# modem.net
KiCad netlist of a schematic drawn in Altium Designer
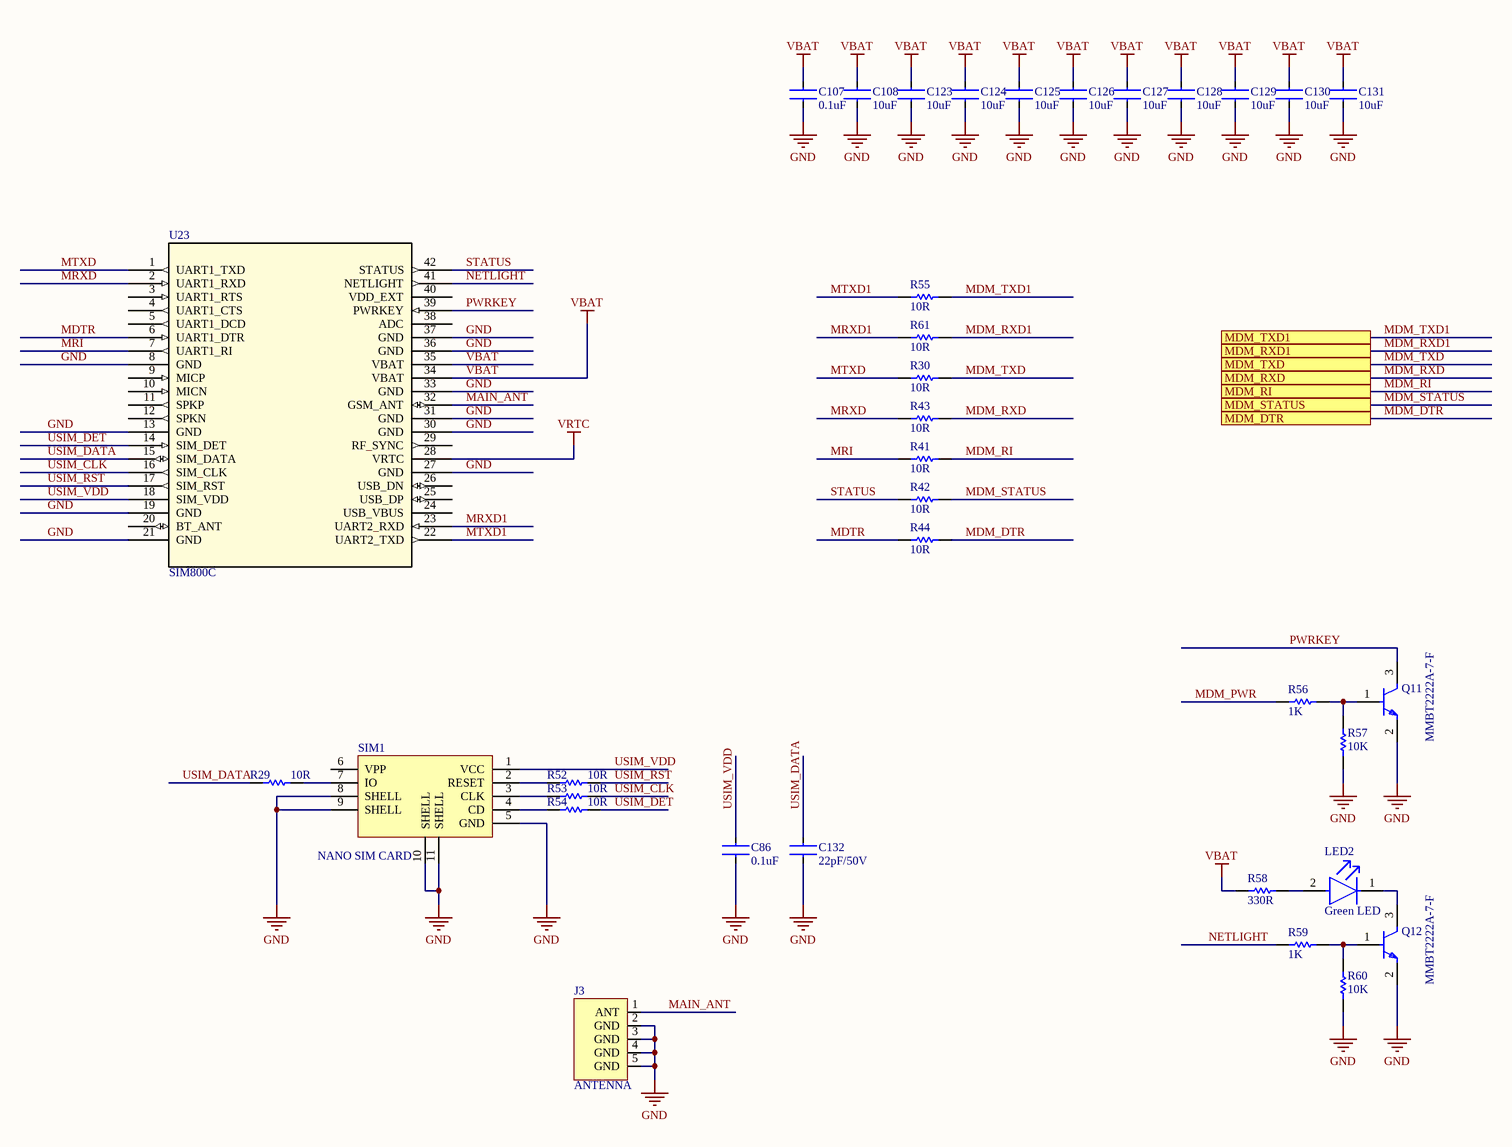
[diagram p0: modem.SchDoc]

(export (version "E")
  (design (tool "Eeschema 10.0.6"))
  (components
    (comp (ref "C86")
      (value "0.1uF")
      (footprint "C0402")
      (description "Ceramic capacitor SMD-1206 100nF /50V X7R# K +-10%, Samsung, RoHS")
      (fields
        (field (name "MANUFACTURER") "Samsung")
        (field (name "MANUFACTURER PART NUMBER") "CL31B104KBCNNNC")
      )
      (libsource (lib "afra") (part "CL31B104KBCNNNC"))
    )
    (comp (ref "C107")
      (value "0.1uF")
      (footprint "C0402")
      (description "Ceramic capacitor SMD-1206 100nF /50V X7R# K +-10%, Samsung, RoHS")
      (fields
        (field (name "MANUFACTURER") "Samsung")
        (field (name "MANUFACTURER PART NUMBER") "CL31B104KBCNNNC")
      )
      (libsource (lib "afra") (part "CL31B104KBCNNNC"))
    )
    (comp (ref "C108")
      (value "10uF")
      (footprint "C0402")
      (description "Cap Ceramic 10uF 16V X7R 10% Pad SMD 1206 125°C T/R")
      (fields
        (field (name "MANUFACTURER") "Samsung")
        (field (name "MANUFACTURER PART NUMBER") "CL31B106KOHNNNE")
      )
      (libsource (lib "afra") (part "CL31B106KOHNNNE"))
    )
    (comp (ref "C123")
      (value "10uF")
      (footprint "C0402")
      (description "Cap Ceramic 10uF 16V X7R 10% Pad SMD 1206 125°C T/R")
      (fields
        (field (name "MANUFACTURER") "Samsung")
        (field (name "MANUFACTURER PART NUMBER") "CL31B106KOHNNNE")
      )
      (libsource (lib "afra") (part "CL31B106KOHNNNE"))
    )
    (comp (ref "C124")
      (value "10uF")
      (footprint "C0402")
      (description "Cap Ceramic 10uF 16V X7R 10% Pad SMD 1206 125°C T/R")
      (fields
        (field (name "MANUFACTURER") "Samsung")
        (field (name "MANUFACTURER PART NUMBER") "CL31B106KOHNNNE")
      )
      (libsource (lib "afra") (part "CL31B106KOHNNNE"))
    )
    (comp (ref "C125")
      (value "10uF")
      (footprint "C0402")
      (description "Cap Ceramic 10uF 16V X7R 10% Pad SMD 1206 125°C T/R")
      (fields
        (field (name "MANUFACTURER") "Samsung")
        (field (name "MANUFACTURER PART NUMBER") "CL31B106KOHNNNE")
      )
      (libsource (lib "afra") (part "CL31B106KOHNNNE"))
    )
    (comp (ref "C126")
      (value "10uF")
      (footprint "C0402")
      (description "Cap Ceramic 10uF 16V X7R 10% Pad SMD 1206 125°C T/R")
      (fields
        (field (name "MANUFACTURER") "Samsung")
        (field (name "MANUFACTURER PART NUMBER") "CL31B106KOHNNNE")
      )
      (libsource (lib "afra") (part "CL31B106KOHNNNE"))
    )
    (comp (ref "C127")
      (value "10uF")
      (footprint "C0402")
      (description "Cap Ceramic 10uF 16V X7R 10% Pad SMD 1206 125°C T/R")
      (fields
        (field (name "MANUFACTURER") "Samsung")
        (field (name "MANUFACTURER PART NUMBER") "CL31B106KOHNNNE")
      )
      (libsource (lib "afra") (part "CL31B106KOHNNNE"))
    )
    (comp (ref "C128")
      (value "10uF")
      (footprint "C0402")
      (description "Cap Ceramic 10uF 16V X7R 10% Pad SMD 1206 125°C T/R")
      (fields
        (field (name "MANUFACTURER") "Samsung")
        (field (name "MANUFACTURER PART NUMBER") "CL31B106KOHNNNE")
      )
      (libsource (lib "afra") (part "CL31B106KOHNNNE"))
    )
    (comp (ref "C129")
      (value "10uF")
      (footprint "C0402")
      (description "Cap Ceramic 10uF 16V X7R 10% Pad SMD 1206 125°C T/R")
      (fields
        (field (name "MANUFACTURER") "Samsung")
        (field (name "MANUFACTURER PART NUMBER") "CL31B106KOHNNNE")
      )
      (libsource (lib "afra") (part "CL31B106KOHNNNE"))
    )
    (comp (ref "C130")
      (value "10uF")
      (footprint "C0402")
      (description "Cap Ceramic 10uF 16V X7R 10% Pad SMD 1206 125°C T/R")
      (fields
        (field (name "MANUFACTURER") "Samsung")
        (field (name "MANUFACTURER PART NUMBER") "CL31B106KOHNNNE")
      )
      (libsource (lib "afra") (part "CL31B106KOHNNNE"))
    )
    (comp (ref "C131")
      (value "10uF")
      (footprint "C0402")
      (description "Cap Ceramic 10uF 16V X7R 10% Pad SMD 1206 125°C T/R")
      (fields
        (field (name "MANUFACTURER") "Samsung")
        (field (name "MANUFACTURER PART NUMBER") "CL31B106KOHNNNE")
      )
      (libsource (lib "afra") (part "CL31B106KOHNNNE"))
    )
    (comp (ref "C132")
      (value "22pF/50V")
      (footprint "C0402")
      (description "Cap Ceramic 22pF 50V C0G 5% SMD 1206 125°C Paper T/R")
      (fields
        (field (name "MANUFACTURER") "Samsung")
        (field (name "MANUFACTURER PART NUMBER") "CL31C220JBCNNNC")
      )
      (libsource (lib "afra") (part "CL31C220JBCNNNC"))
    )
    (comp (ref "J3") (value "ANTENNA") (footprint "Antenna") (libsource (lib "afra") (part "antenna")))
    (comp (ref "LED2")
      (value "Green LED")
      (footprint "SMD_LED_1206")
      (description "LED GREEN CLEAR 1206 SMD")
      (fields
        (field (name "MANUFACTURER") "Vishay Lite-On")
        (field (name "MANUFACTURER PART NUMBER") "LTST-C150GKT")
      )
      (libsource (lib "afra") (part "LTST-C150GKT"))
    )
    (comp (ref "Q11")
      (value "MMBT2222A-7-F")
      (footprint "SOT-23-3L_AOS")
      (description "NPN Ic=600mA Vceo=40V hfe=100~300 fT=300MHz P=310mW SOT-23")
      (fields (field (name "MANUFACTURER") "Diodes") (field (name "VOLTAGE") "40V"))
      (libsource (lib "afra") (part "MMBT2222A-7-F"))
    )
    (comp (ref "Q12")
      (value "MMBT2222A-7-F")
      (footprint "SOT-23-3L_AOS")
      (description "NPN Ic=600mA Vceo=40V hfe=100~300 fT=300MHz P=310mW SOT-23")
      (fields (field (name "MANUFACTURER") "Diodes") (field (name "VOLTAGE") "40V"))
      (libsource (lib "afra") (part "MMBT2222A-7-F"))
    )
    (comp (ref "R29")
      (value "10R")
      (footprint "R0402")
      (description "Res Thick Film 1206 10 Ohm 1% 0.25W(1/4W) +/-200ppm/ßC Epoxy SMD T/R")
      (fields
        (field (name "MANUFACTURER") "Yageo")
        (field (name "MANUFACTURER PART NUMBER") "RC1206FR-0710RL")
      )
      (libsource (lib "afra") (part "RC1206FR-0710RL"))
    )
    (comp (ref "R30")
      (value "10R")
      (footprint "R0402")
      (description "Res Thick Film 1206 10 Ohm 1% 0.25W(1/4W) +/-200ppm/ßC Epoxy SMD T/R")
      (fields
        (field (name "MANUFACTURER") "Yageo")
        (field (name "MANUFACTURER PART NUMBER") "RC1206FR-0710RL")
      )
      (libsource (lib "afra") (part "RC1206FR-0710RL"))
    )
    (comp (ref "R41")
      (value "10R")
      (footprint "R0402")
      (description "Res Thick Film 1206 10 Ohm 1% 0.25W(1/4W) +/-200ppm/ßC Epoxy SMD T/R")
      (fields
        (field (name "MANUFACTURER") "Yageo")
        (field (name "MANUFACTURER PART NUMBER") "RC1206FR-0710RL")
      )
      (libsource (lib "afra") (part "RC1206FR-0710RL"))
    )
    (comp (ref "R42")
      (value "10R")
      (footprint "R0402")
      (description "Res Thick Film 1206 10 Ohm 1% 0.25W(1/4W) +/-200ppm/ßC Epoxy SMD T/R")
      (fields
        (field (name "MANUFACTURER") "Yageo")
        (field (name "MANUFACTURER PART NUMBER") "RC1206FR-0710RL")
      )
      (libsource (lib "afra") (part "RC1206FR-0710RL"))
    )
    (comp (ref "R43")
      (value "10R")
      (footprint "R0402")
      (description "Res Thick Film 1206 10 Ohm 1% 0.25W(1/4W) +/-200ppm/ßC Epoxy SMD T/R")
      (fields
        (field (name "MANUFACTURER") "Yageo")
        (field (name "MANUFACTURER PART NUMBER") "RC1206FR-0710RL")
      )
      (libsource (lib "afra") (part "RC1206FR-0710RL"))
    )
    (comp (ref "R44")
      (value "10R")
      (footprint "R0402")
      (description "Res Thick Film 1206 10 Ohm 1% 0.25W(1/4W) +/-200ppm/ßC Epoxy SMD T/R")
      (fields
        (field (name "MANUFACTURER") "Yageo")
        (field (name "MANUFACTURER PART NUMBER") "RC1206FR-0710RL")
      )
      (libsource (lib "afra") (part "RC1206FR-0710RL"))
    )
    (comp (ref "R52")
      (value "10R")
      (footprint "R0402")
      (description "Res Thick Film 1206 10 Ohm 1% 0.25W(1/4W) +/-200ppm/ßC Epoxy SMD T/R")
      (fields
        (field (name "MANUFACTURER") "Yageo")
        (field (name "MANUFACTURER PART NUMBER") "RC1206FR-0710RL")
      )
      (libsource (lib "afra") (part "RC1206FR-0710RL"))
    )
    (comp (ref "R53")
      (value "10R")
      (footprint "R0402")
      (description "Res Thick Film 1206 10 Ohm 1% 0.25W(1/4W) +/-200ppm/ßC Epoxy SMD T/R")
      (fields
        (field (name "MANUFACTURER") "Yageo")
        (field (name "MANUFACTURER PART NUMBER") "RC1206FR-0710RL")
      )
      (libsource (lib "afra") (part "RC1206FR-0710RL"))
    )
    (comp (ref "R54")
      (value "10R")
      (footprint "R0402")
      (description "Res Thick Film 1206 10 Ohm 1% 0.25W(1/4W) +/-200ppm/ßC Epoxy SMD T/R")
      (fields
        (field (name "MANUFACTURER") "Yageo")
        (field (name "MANUFACTURER PART NUMBER") "RC1206FR-0710RL")
      )
      (libsource (lib "afra") (part "RC1206FR-0710RL"))
    )
    (comp (ref "R55")
      (value "10R")
      (footprint "R0402")
      (description "Res Thick Film 1206 10 Ohm 1% 0.25W(1/4W) +/-200ppm/ßC Epoxy SMD T/R")
      (fields
        (field (name "MANUFACTURER") "Yageo")
        (field (name "MANUFACTURER PART NUMBER") "RC1206FR-0710RL")
      )
      (libsource (lib "afra") (part "RC1206FR-0710RL"))
    )
    (comp (ref "R56")
      (value "1K")
      (footprint "R0402")
      (description "In a Pack of 5000, 1K 1206 Thick Film SMD Resistor ±1% 0.25W - RC1206FR-071KL")
      (fields
        (field (name "MANUFACTURER") "Yageo")
        (field (name "MANUFACTURER PART NUMBER") "RC1206FR-071KL")
      )
      (libsource (lib "afra") (part "RC1206FR-071KL"))
    )
    (comp (ref "R57")
      (value "10K")
      (footprint "R0402")
      (description "Res Thick Film 1206 10K Ohm 1% 0.25W(1/4W) ±100ppm/C Pad SMD T/R")
      (fields
        (field (name "MANUFACTURER") "Yageo")
        (field (name "MANUFACTURER PART NUMBER") "RC1206FR-0710KL")
      )
      (libsource (lib "afra") (part "RC1206FR-0710KL"))
    )
    (comp (ref "R58")
      (value "330R")
      (footprint "R0402")
      (description "Res Thick Film 1206 330 Ohm 1% 0.25W(1/4W) ±100ppm/°C Pad SMD T/R")
      (fields
        (field (name "MANUFACTURER") "Yageo")
        (field (name "MANUFACTURER PART NUMBER") "RC1206FR-07330RL")
      )
      (libsource (lib "afra") (part "RC1206FR-07330RL"))
    )
    (comp (ref "R59")
      (value "1K")
      (footprint "R0402")
      (description "In a Pack of 5000, 1K 1206 Thick Film SMD Resistor ±1% 0.25W - RC1206FR-071KL")
      (fields
        (field (name "MANUFACTURER") "Yageo")
        (field (name "MANUFACTURER PART NUMBER") "RC1206FR-071KL")
      )
      (libsource (lib "afra") (part "RC1206FR-071KL"))
    )
    (comp (ref "R60")
      (value "10K")
      (footprint "R0402")
      (description "Res Thick Film 1206 10K Ohm 1% 0.25W(1/4W) ±100ppm/C Pad SMD T/R")
      (fields
        (field (name "MANUFACTURER") "Yageo")
        (field (name "MANUFACTURER PART NUMBER") "RC1206FR-0710KL")
      )
      (libsource (lib "afra") (part "RC1206FR-0710KL"))
    )
    (comp (ref "R61")
      (value "10R")
      (footprint "R0402")
      (description "Res Thick Film 1206 10 Ohm 1% 0.25W(1/4W) +/-200ppm/ßC Epoxy SMD T/R")
      (fields
        (field (name "MANUFACTURER") "Yageo")
        (field (name "MANUFACTURER PART NUMBER") "RC1206FR-0710RL")
      )
      (libsource (lib "afra") (part "RC1206FR-0710RL"))
    )
    (comp (ref "SIM1")
      (value "NANO SIM CARD")
      (footprint "Nano Sim")
      (libsource (lib "afra") (part "Nano sim"))
    )
    (comp (ref "U23")
      (value "SIM800C")
      (footprint "SIM800C_SMM")
      (description "No Description Available")
      (fields (field (name "COPYRIGHT") "Copyright (C) 2022 Ultra Librarian. All rights reserved."))
      (libsource (lib "afra") (part "SIM800C"))
    )
  )
  (nets
    (net (code "1") (name "/MAIN_ANT") (class "Default")
      (node (ref "J3") (pin "1") (pinfunction "ANT_1") (pintype "passive"))
      (node (ref "U23") (pin "32") (pinfunction "GSM_ANT_32") (pintype "bidirectional"))
    )
    (net (code "2") (name "/MDM_DTR") (class "Default")
      (node (ref "R44") (pin "2") (pinfunction "2_2") (pintype "passive"))
    )
    (net (code "3") (name "/MDM_PWR") (class "Default")
      (node (ref "R56") (pin "1") (pinfunction "1_1") (pintype "passive"))
    )
    (net (code "4") (name "/MDM_RI") (class "Default")
      (node (ref "R41") (pin "2") (pinfunction "2_2") (pintype "passive"))
    )
    (net (code "5") (name "/MDM_RXD") (class "Default")
      (node (ref "R43") (pin "2") (pinfunction "2_2") (pintype "passive"))
    )
    (net (code "6") (name "/MDM_RXD1") (class "Default")
      (node (ref "R61") (pin "2") (pinfunction "2_2") (pintype "passive"))
    )
    (net (code "7") (name "/MDM_STATUS") (class "Default")
      (node (ref "R42") (pin "2") (pinfunction "2_2") (pintype "passive"))
    )
    (net (code "8") (name "/MDM_TXD") (class "Default")
      (node (ref "R30") (pin "2") (pinfunction "2_2") (pintype "passive"))
    )
    (net (code "9") (name "/MDM_TXD1") (class "Default")
      (node (ref "R55") (pin "2") (pinfunction "2_2") (pintype "passive"))
    )
    (net (code "10") (name "/MDTR") (class "Default")
      (node (ref "R44") (pin "1") (pinfunction "1_1") (pintype "passive"))
      (node (ref "U23") (pin "6") (pinfunction "UART1_DTR_6") (pintype "input"))
    )
    (net (code "11") (name "/MRI") (class "Default")
      (node (ref "R41") (pin "1") (pinfunction "1_1") (pintype "passive"))
      (node (ref "U23") (pin "7") (pinfunction "UART1_RI_7") (pintype "output"))
    )
    (net (code "12") (name "/MRXD") (class "Default")
      (node (ref "R43") (pin "1") (pinfunction "1_1") (pintype "passive"))
      (node (ref "U23") (pin "2") (pinfunction "UART1_RXD_2") (pintype "input"))
    )
    (net (code "13") (name "/MRXD1") (class "Default")
      (node (ref "R61") (pin "1") (pinfunction "1_1") (pintype "passive"))
      (node (ref "U23") (pin "23") (pinfunction "UART2_RXD_23") (pintype "input"))
    )
    (net (code "14") (name "/MTXD") (class "Default")
      (node (ref "R30") (pin "1") (pinfunction "1_1") (pintype "passive"))
      (node (ref "U23") (pin "1") (pinfunction "UART1_TXD_1") (pintype "output"))
    )
    (net (code "15") (name "/MTXD1") (class "Default")
      (node (ref "R55") (pin "1") (pinfunction "1_1") (pintype "passive"))
      (node (ref "U23") (pin "22") (pinfunction "UART2_TXD_22") (pintype "output"))
    )
    (net (code "16") (name "/NETLIGHT") (class "Default")
      (node (ref "R59") (pin "1") (pinfunction "1_1") (pintype "passive"))
      (node (ref "U23") (pin "41") (pinfunction "NETLIGHT_41") (pintype "output"))
    )
    (net (code "17") (name "/PWRKEY") (class "Default")
      (node (ref "Q11") (pin "3") (pinfunction "C_3") (pintype "passive"))
      (node (ref "U23") (pin "39") (pinfunction "PWRKEY_39") (pintype "input"))
    )
    (net (code "18") (name "/STATUS") (class "Default")
      (node (ref "R42") (pin "1") (pinfunction "1_1") (pintype "passive"))
      (node (ref "U23") (pin "42") (pinfunction "STATUS_42") (pintype "output"))
    )
    (net (code "19") (name "/USIM_CLK") (class "Default")
      (node (ref "R53") (pin "2") (pinfunction "2_2") (pintype "passive"))
      (node (ref "U23") (pin "16") (pinfunction "SIM_CLK_16") (pintype "output"))
    )
    (net (code "20") (name "/USIM_DATA") (class "Default")
      (node (ref "C132") (pin "1") (pinfunction "1_1") (pintype "passive"))
      (node (ref "R29") (pin "1") (pinfunction "1_1") (pintype "passive"))
      (node (ref "U23") (pin "15") (pinfunction "SIM_DATA_15") (pintype "bidirectional"))
    )
    (net (code "21") (name "/USIM_DET") (class "Default")
      (node (ref "R54") (pin "2") (pinfunction "2_2") (pintype "passive"))
      (node (ref "U23") (pin "14") (pinfunction "SIM_DET_14") (pintype "input"))
    )
    (net (code "22") (name "/USIM_RST") (class "Default")
      (node (ref "R52") (pin "2") (pinfunction "2_2") (pintype "passive"))
      (node (ref "U23") (pin "17") (pinfunction "SIM_RST_17") (pintype "output"))
    )
    (net (code "23") (name "/USIM_VDD") (class "Default")
      (node (ref "C86") (pin "1") (pinfunction "1_1") (pintype "passive"))
      (node (ref "SIM1") (pin "1") (pinfunction "VCC_1") (pintype "passive"))
      (node (ref "U23") (pin "18") (pinfunction "SIM_VDD_18") (pintype "power_in"))
    )
    (net (code "24") (name "GND") (class "Default")
      (node (ref "C107") (pin "2") (pinfunction "2_2") (pintype "passive"))
      (node (ref "C108") (pin "2") (pinfunction "2_2") (pintype "passive"))
      (node (ref "C123") (pin "2") (pinfunction "2_2") (pintype "passive"))
      (node (ref "C124") (pin "2") (pinfunction "2_2") (pintype "passive"))
      (node (ref "C125") (pin "2") (pinfunction "2_2") (pintype "passive"))
      (node (ref "C126") (pin "2") (pinfunction "2_2") (pintype "passive"))
      (node (ref "C127") (pin "2") (pinfunction "2_2") (pintype "passive"))
      (node (ref "C128") (pin "2") (pinfunction "2_2") (pintype "passive"))
      (node (ref "C129") (pin "2") (pinfunction "2_2") (pintype "passive"))
      (node (ref "C130") (pin "2") (pinfunction "2_2") (pintype "passive"))
      (node (ref "C131") (pin "2") (pinfunction "2_2") (pintype "passive"))
      (node (ref "C132") (pin "2") (pinfunction "2_2") (pintype "passive"))
      (node (ref "C86") (pin "2") (pinfunction "2_2") (pintype "passive"))
      (node (ref "J3") (pin "2") (pinfunction "GND_2") (pintype "passive"))
      (node (ref "J3") (pin "3") (pinfunction "GND_3") (pintype "passive"))
      (node (ref "J3") (pin "4") (pinfunction "GND_4") (pintype "passive"))
      (node (ref "J3") (pin "5") (pinfunction "GND_5") (pintype "passive"))
      (node (ref "Q11") (pin "2") (pinfunction "E_2") (pintype "passive"))
      (node (ref "Q12") (pin "2") (pinfunction "E_2") (pintype "passive"))
      (node (ref "R57") (pin "1") (pinfunction "1_1") (pintype "passive"))
      (node (ref "R60") (pin "1") (pinfunction "1_1") (pintype "passive"))
      (node (ref "SIM1") (pin "10") (pinfunction "SHELL_10") (pintype "passive"))
      (node (ref "SIM1") (pin "11") (pinfunction "SHELL_11") (pintype "passive"))
      (node (ref "SIM1") (pin "5") (pinfunction "GND_5") (pintype "passive"))
      (node (ref "SIM1") (pin "8") (pinfunction "SHELL_8") (pintype "passive"))
      (node (ref "SIM1") (pin "9") (pinfunction "SHELL_9") (pintype "passive"))
      (node (ref "U23") (pin "13") (pinfunction "GND_13") (pintype "passive"))
      (node (ref "U23") (pin "19") (pinfunction "GND_19") (pintype "passive"))
      (node (ref "U23") (pin "21") (pinfunction "GND_21") (pintype "passive"))
      (node (ref "U23") (pin "27") (pinfunction "GND_27") (pintype "passive"))
      (node (ref "U23") (pin "30") (pinfunction "GND_30") (pintype "passive"))
      (node (ref "U23") (pin "31") (pinfunction "GND_31") (pintype "passive"))
      (node (ref "U23") (pin "33") (pinfunction "GND_33") (pintype "passive"))
      (node (ref "U23") (pin "36") (pinfunction "GND_36") (pintype "passive"))
      (node (ref "U23") (pin "37") (pinfunction "GND_37") (pintype "passive"))
      (node (ref "U23") (pin "8") (pinfunction "GND_8") (pintype "passive"))
    )
    (net (code "25") (name "Net-(LED2-A)") (class "Default")
      (node (ref "LED2") (pin "2") (pinfunction "A_2") (pintype "passive"))
      (node (ref "R58") (pin "2") (pinfunction "2_2") (pintype "passive"))
    )
    (net (code "26") (name "Net-(LED2-C)") (class "Default")
      (node (ref "LED2") (pin "1") (pinfunction "C_1") (pintype "passive"))
      (node (ref "Q12") (pin "3") (pinfunction "C_3") (pintype "passive"))
    )
    (net (code "27") (name "Net-(Q11-B)") (class "Default")
      (node (ref "Q11") (pin "1") (pinfunction "B_1") (pintype "passive"))
      (node (ref "R56") (pin "2") (pinfunction "2_2") (pintype "passive"))
      (node (ref "R57") (pin "2") (pinfunction "2_2") (pintype "passive"))
    )
    (net (code "28") (name "Net-(Q12-B)") (class "Default")
      (node (ref "Q12") (pin "1") (pinfunction "B_1") (pintype "passive"))
      (node (ref "R59") (pin "2") (pinfunction "2_2") (pintype "passive"))
      (node (ref "R60") (pin "2") (pinfunction "2_2") (pintype "passive"))
    )
    (net (code "29") (name "Net-(SIM1-CD)") (class "Default")
      (node (ref "R54") (pin "1") (pinfunction "1_1") (pintype "passive"))
      (node (ref "SIM1") (pin "4") (pinfunction "CD_4") (pintype "passive"))
    )
    (net (code "30") (name "Net-(SIM1-CLK)") (class "Default")
      (node (ref "R53") (pin "1") (pinfunction "1_1") (pintype "passive"))
      (node (ref "SIM1") (pin "3") (pinfunction "CLK_3") (pintype "passive"))
    )
    (net (code "31") (name "Net-(SIM1-IO)") (class "Default")
      (node (ref "R29") (pin "2") (pinfunction "2_2") (pintype "passive"))
      (node (ref "SIM1") (pin "7") (pinfunction "IO_7") (pintype "passive"))
    )
    (net (code "32") (name "Net-(SIM1-RESET)") (class "Default")
      (node (ref "R52") (pin "1") (pinfunction "1_1") (pintype "passive"))
      (node (ref "SIM1") (pin "2") (pinfunction "RESET_2") (pintype "passive"))
    )
    (net (code "33") (name "VBAT") (class "Default")
      (node (ref "C107") (pin "1") (pinfunction "1_1") (pintype "passive"))
      (node (ref "C108") (pin "1") (pinfunction "1_1") (pintype "passive"))
      (node (ref "C123") (pin "1") (pinfunction "1_1") (pintype "passive"))
      (node (ref "C124") (pin "1") (pinfunction "1_1") (pintype "passive"))
      (node (ref "C125") (pin "1") (pinfunction "1_1") (pintype "passive"))
      (node (ref "C126") (pin "1") (pinfunction "1_1") (pintype "passive"))
      (node (ref "C127") (pin "1") (pinfunction "1_1") (pintype "passive"))
      (node (ref "C128") (pin "1") (pinfunction "1_1") (pintype "passive"))
      (node (ref "C129") (pin "1") (pinfunction "1_1") (pintype "passive"))
      (node (ref "C130") (pin "1") (pinfunction "1_1") (pintype "passive"))
      (node (ref "C131") (pin "1") (pinfunction "1_1") (pintype "passive"))
      (node (ref "R58") (pin "1") (pinfunction "1_1") (pintype "passive"))
      (node (ref "U23") (pin "34") (pinfunction "VBAT_34") (pintype "power_in"))
      (node (ref "U23") (pin "35") (pinfunction "VBAT_35") (pintype "power_in"))
    )
    (net (code "34") (name "VRTC") (class "Default")
      (node (ref "U23") (pin "28") (pinfunction "VRTC_28") (pintype "power_in"))
    )
    (net (code "35") (name "unconnected-(SIM1-VPP-Pad6)") (class "Default")
      (node (ref "SIM1") (pin "6") (pinfunction "VPP_6") (pintype "passive"))
    )
    (net (code "36") (name "unconnected-(U23-ADC-Pad38)") (class "Default")
      (node (ref "U23") (pin "38") (pinfunction "ADC_38") (pintype "passive"))
    )
    (net (code "37") (name "unconnected-(U23-BT_ANT-Pad20)") (class "Default")
      (node (ref "U23") (pin "20") (pinfunction "BT_ANT_20") (pintype "bidirectional"))
    )
    (net (code "38") (name "unconnected-(U23-MICN-Pad10)") (class "Default")
      (node (ref "U23") (pin "10") (pinfunction "MICN_10") (pintype "input"))
    )
    (net (code "39") (name "unconnected-(U23-MICP-Pad9)") (class "Default")
      (node (ref "U23") (pin "9") (pinfunction "MICP_9") (pintype "input"))
    )
    (net (code "40") (name "unconnected-(U23-RF_SYNC-Pad29)") (class "Default")
      (node (ref "U23") (pin "29") (pinfunction "RF_SYNC_29") (pintype "output"))
    )
    (net (code "41") (name "unconnected-(U23-SPKN-Pad12)") (class "Default")
      (node (ref "U23") (pin "12") (pinfunction "SPKN_12") (pintype "output"))
    )
    (net (code "42") (name "unconnected-(U23-SPKP-Pad11)") (class "Default")
      (node (ref "U23") (pin "11") (pinfunction "SPKP_11") (pintype "output"))
    )
    (net (code "43") (name "unconnected-(U23-UART1_CTS-Pad4)") (class "Default")
      (node (ref "U23") (pin "4") (pinfunction "UART1_CTS_4") (pintype "output"))
    )
    (net (code "44") (name "unconnected-(U23-UART1_DCD-Pad5)") (class "Default")
      (node (ref "U23") (pin "5") (pinfunction "UART1_DCD_5") (pintype "output"))
    )
    (net (code "45") (name "unconnected-(U23-UART1_RTS-Pad3)") (class "Default")
      (node (ref "U23") (pin "3") (pinfunction "UART1_RTS_3") (pintype "input"))
    )
    (net (code "46") (name "unconnected-(U23-USB_DN-Pad26)") (class "Default")
      (node (ref "U23") (pin "26") (pinfunction "USB_DN_26") (pintype "bidirectional"))
    )
    (net (code "47") (name "unconnected-(U23-USB_DP-Pad25)") (class "Default")
      (node (ref "U23") (pin "25") (pinfunction "USB_DP_25") (pintype "bidirectional"))
    )
    (net (code "48") (name "unconnected-(U23-USB_VBUS-Pad24)") (class "Default")
      (node (ref "U23") (pin "24") (pinfunction "USB_VBUS_24") (pintype "power_in"))
    )
    (net (code "49") (name "unconnected-(U23-VDD_EXT-Pad40)") (class "Default")
      (node (ref "U23") (pin "40") (pinfunction "VDD_EXT_40") (pintype "power_in"))
    )
  )
)
